# 2out_servo_2te.net
KiCad netlist of a schematic drawn in EAGLE
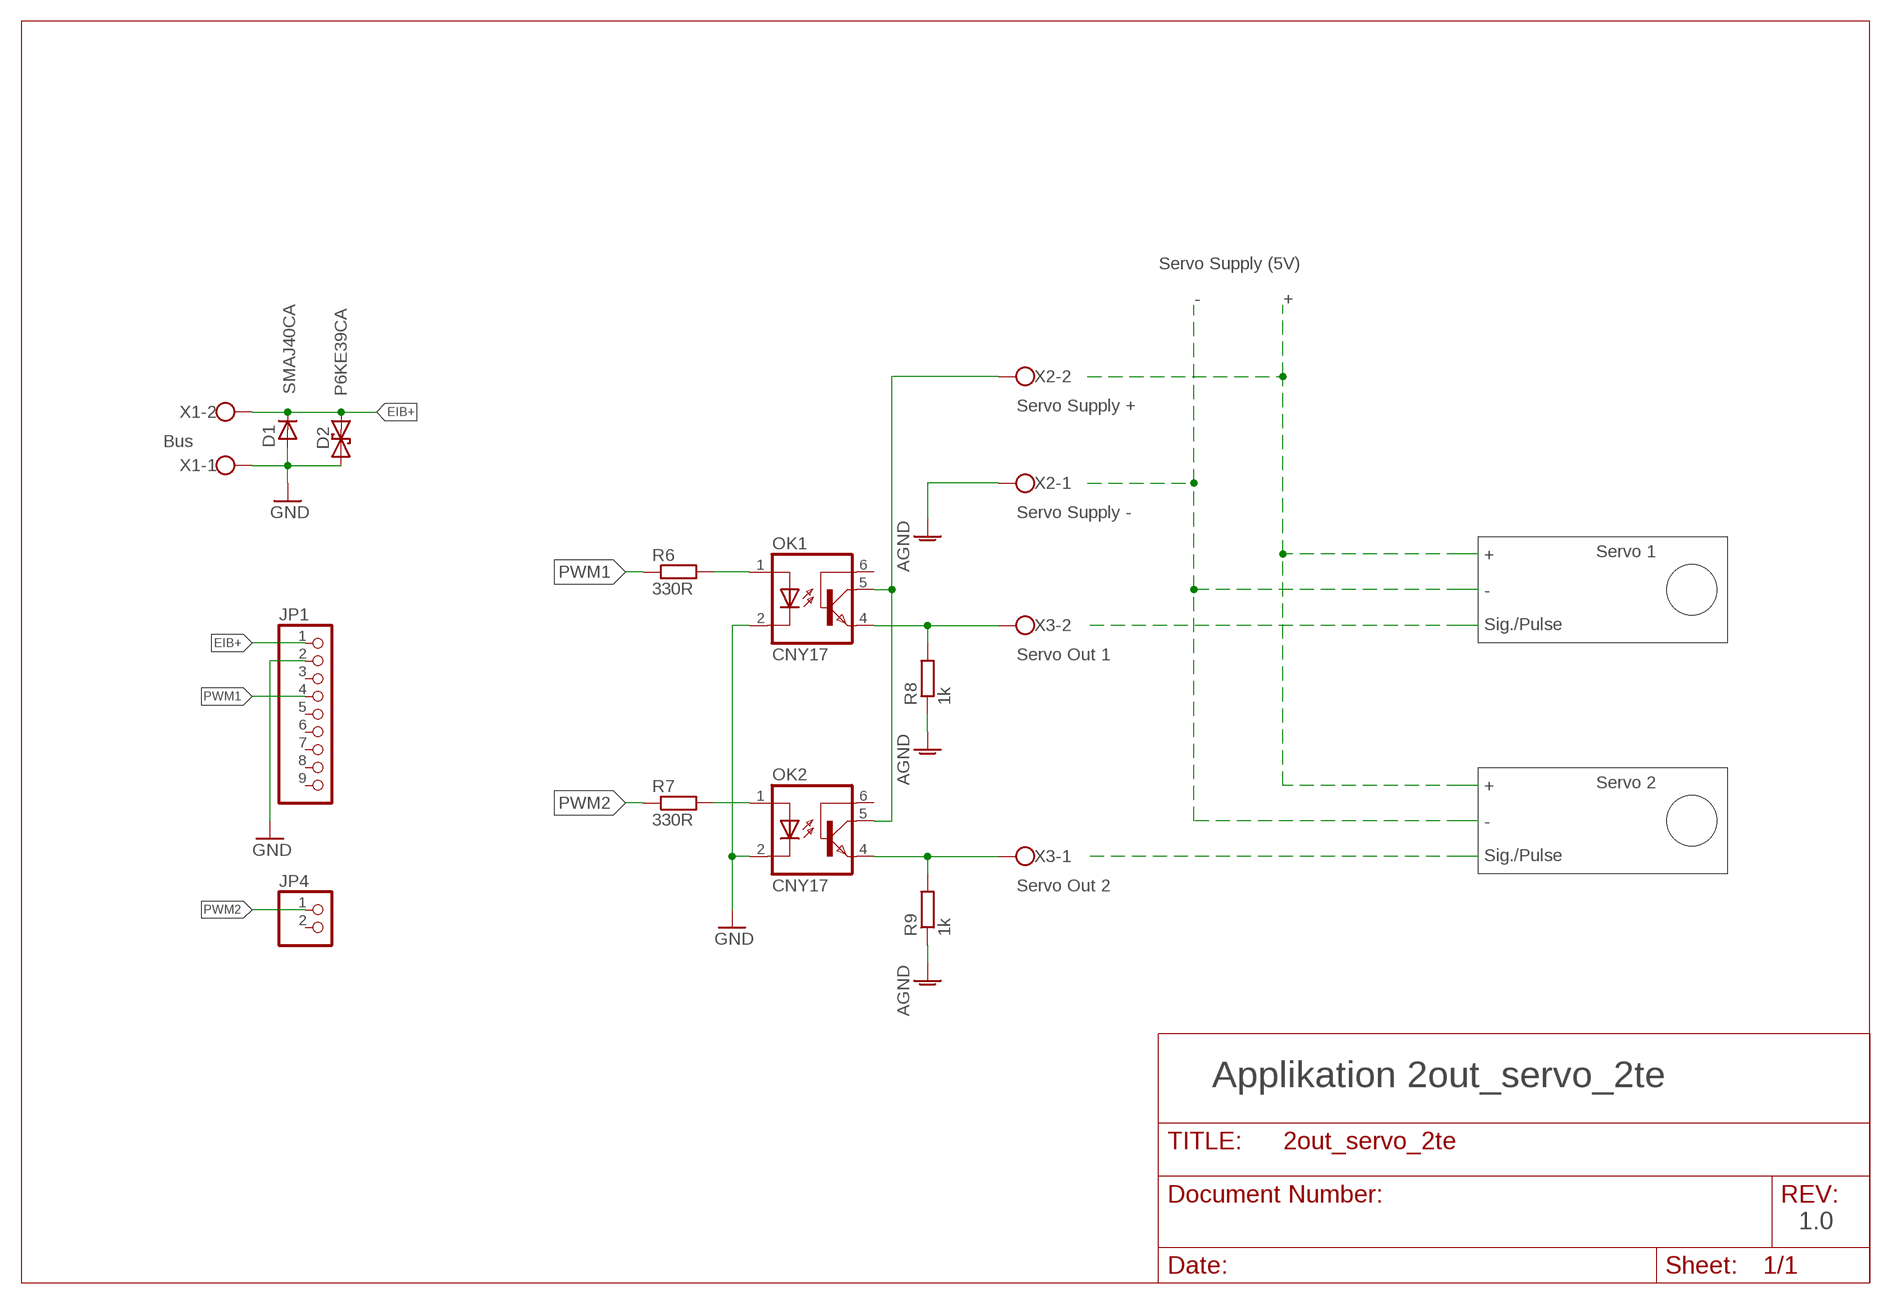
[diagram p0: schematic, sheet 1]

(export (version "E")
  (design (tool "Eeschema 10.0.6"))
  (components
    (comp (ref "D1")
      (value "SMAJ40CA")
      (footprint "eagle-import:SOD87")
      (libsource (lib "eagle-import") (part "D-SOD-87"))
    )
    (comp (ref "D2")
      (value "P6KE39CA")
      (footprint "eagle-import:DO41-7")
      (libsource (lib "eagle-import") (part "P6KEXXCDO41-7"))
    )
    (comp (ref "JP1")
      (value "PINHD-1X9")
      (footprint "eagle-import:1X09")
      (libsource (lib "eagle-import") (part "PINHD-1X9"))
    )
    (comp (ref "JP4")
      (value "PINHD-1X2")
      (footprint "eagle-import:1X02")
      (libsource (lib "eagle-import") (part "PINHD-1X2"))
    )
    (comp (ref "OK1")
      (value "CNY17")
      (footprint "eagle-import:DIL06")
      (fields (field (name "MPN") "CNY17-1"))
      (libsource (lib "eagle-import") (part "CNY17"))
    )
    (comp (ref "OK2")
      (value "CNY17")
      (footprint "eagle-import:DIL06")
      (fields (field (name "MPN") "CNY17-1"))
      (libsource (lib "eagle-import") (part "CNY17"))
    )
    (comp (ref "R6")
      (value "330R")
      (footprint "eagle-import:0207_7")
      (libsource (lib "eagle-import") (part "R-EU_0207/7"))
    )
    (comp (ref "R7")
      (value "330R")
      (footprint "eagle-import:0207_7")
      (libsource (lib "eagle-import") (part "R-EU_0207/7"))
    )
    (comp (ref "R8")
      (value "1k")
      (footprint "eagle-import:0207_7")
      (libsource (lib "eagle-import") (part "R-EU_0207/7"))
    )
    (comp (ref "R9")
      (value "1k")
      (footprint "eagle-import:0207_7")
      (libsource (lib "eagle-import") (part "R-EU_0207/7"))
    )
    (comp (ref "X1")
      (value "W237-02P")
      (footprint "eagle-import:W237-132")
      (libsource (lib "eagle-import") (part "W237-02P"))
    )
    (comp (ref "X2")
      (value "W237-02P")
      (footprint "eagle-import:W237-132")
      (libsource (lib "eagle-import") (part "W237-02P"))
    )
    (comp (ref "X3")
      (value "W237-02P")
      (footprint "eagle-import:W237-132")
      (libsource (lib "eagle-import") (part "W237-02P"))
    )
  )
  (nets
    (net (code "1") (name "AGND") (class "Default")
      (node (ref "R8") (pin "1") (pinfunction "1_1") (pintype "passive"))
      (node (ref "R9") (pin "1") (pinfunction "1_1") (pintype "passive"))
      (node (ref "X2") (pin "1") (pinfunction "KL_1") (pintype "passive"))
    )
    (net (code "2") (name "EIB+") (class "Default")
      (node (ref "D1") (pin "1") (pinfunction "C_1") (pintype "passive"))
      (node (ref "D2") (pin "C") (pinfunction "2_C") (pintype "passive"))
      (node (ref "JP1") (pin "1") (pinfunction "1_1") (pintype "passive"))
      (node (ref "X1") (pin "2") (pinfunction "KL_2") (pintype "passive"))
    )
    (net (code "3") (name "GND") (class "Default")
      (node (ref "D1") (pin "2") (pinfunction "A_2") (pintype "passive"))
      (node (ref "D2") (pin "A") (pinfunction "1_A") (pintype "passive"))
      (node (ref "JP1") (pin "2") (pinfunction "2_2") (pintype "passive"))
      (node (ref "OK1") (pin "2") (pinfunction "C_2") (pintype "passive"))
      (node (ref "OK2") (pin "2") (pinfunction "C_2") (pintype "passive"))
      (node (ref "X1") (pin "1") (pinfunction "KL_1") (pintype "passive"))
    )
    (net (code "4") (name "Net-(OK1-A)") (class "Default")
      (node (ref "OK1") (pin "1") (pinfunction "A_1") (pintype "passive"))
      (node (ref "R6") (pin "2") (pinfunction "2_2") (pintype "passive"))
    )
    (net (code "5") (name "Net-(OK1-COL)") (class "Default")
      (node (ref "OK1") (pin "5") (pinfunction "COL_5") (pintype "passive"))
      (node (ref "OK2") (pin "5") (pinfunction "COL_5") (pintype "passive"))
      (node (ref "X2") (pin "2") (pinfunction "KL_2") (pintype "passive"))
    )
    (net (code "6") (name "Net-(OK1-EMI)") (class "Default")
      (node (ref "OK1") (pin "4") (pinfunction "EMI_4") (pintype "passive"))
      (node (ref "R8") (pin "2") (pinfunction "2_2") (pintype "passive"))
      (node (ref "X3") (pin "2") (pinfunction "KL_2") (pintype "passive"))
    )
    (net (code "7") (name "Net-(OK2-A)") (class "Default")
      (node (ref "OK2") (pin "1") (pinfunction "A_1") (pintype "passive"))
      (node (ref "R7") (pin "2") (pinfunction "2_2") (pintype "passive"))
    )
    (net (code "8") (name "Net-(OK2-EMI)") (class "Default")
      (node (ref "OK2") (pin "4") (pinfunction "EMI_4") (pintype "passive"))
      (node (ref "R9") (pin "2") (pinfunction "2_2") (pintype "passive"))
      (node (ref "X3") (pin "1") (pinfunction "KL_1") (pintype "passive"))
    )
    (net (code "9") (name "PWM1") (class "Default")
      (node (ref "JP1") (pin "4") (pinfunction "4_4") (pintype "passive"))
      (node (ref "R6") (pin "1") (pinfunction "1_1") (pintype "passive"))
    )
    (net (code "10") (name "PWM2") (class "Default")
      (node (ref "JP4") (pin "1") (pinfunction "1_1") (pintype "passive"))
      (node (ref "R7") (pin "1") (pinfunction "1_1") (pintype "passive"))
    )
    (net (code "11") (name "unconnected-(JP1-Pad3)") (class "Default")
      (node (ref "JP1") (pin "3") (pinfunction "3_3") (pintype "passive"))
    )
    (net (code "12") (name "unconnected-(JP1-Pad5)") (class "Default")
      (node (ref "JP1") (pin "5") (pinfunction "5_5") (pintype "passive"))
    )
    (net (code "13") (name "unconnected-(JP1-Pad6)") (class "Default")
      (node (ref "JP1") (pin "6") (pinfunction "6_6") (pintype "passive"))
    )
    (net (code "14") (name "unconnected-(JP1-Pad7)") (class "Default")
      (node (ref "JP1") (pin "7") (pinfunction "7_7") (pintype "passive"))
    )
    (net (code "15") (name "unconnected-(JP1-Pad8)") (class "Default")
      (node (ref "JP1") (pin "8") (pinfunction "8_8") (pintype "passive"))
    )
    (net (code "16") (name "unconnected-(JP1-Pad9)") (class "Default")
      (node (ref "JP1") (pin "9") (pinfunction "9_9") (pintype "passive"))
    )
    (net (code "17") (name "unconnected-(JP4-Pad2)") (class "Default")
      (node (ref "JP4") (pin "2") (pinfunction "2_2") (pintype "passive"))
    )
    (net (code "18") (name "unconnected-(OK1-BAS-Pad6)") (class "Default")
      (node (ref "OK1") (pin "6") (pinfunction "BAS_6") (pintype "passive"))
    )
    (net (code "19") (name "unconnected-(OK2-BAS-Pad6)") (class "Default")
      (node (ref "OK2") (pin "6") (pinfunction "BAS_6") (pintype "passive"))
    )
  )
)
